# Sheet.net
KiCad netlist of a schematic drawn in Altium Designer
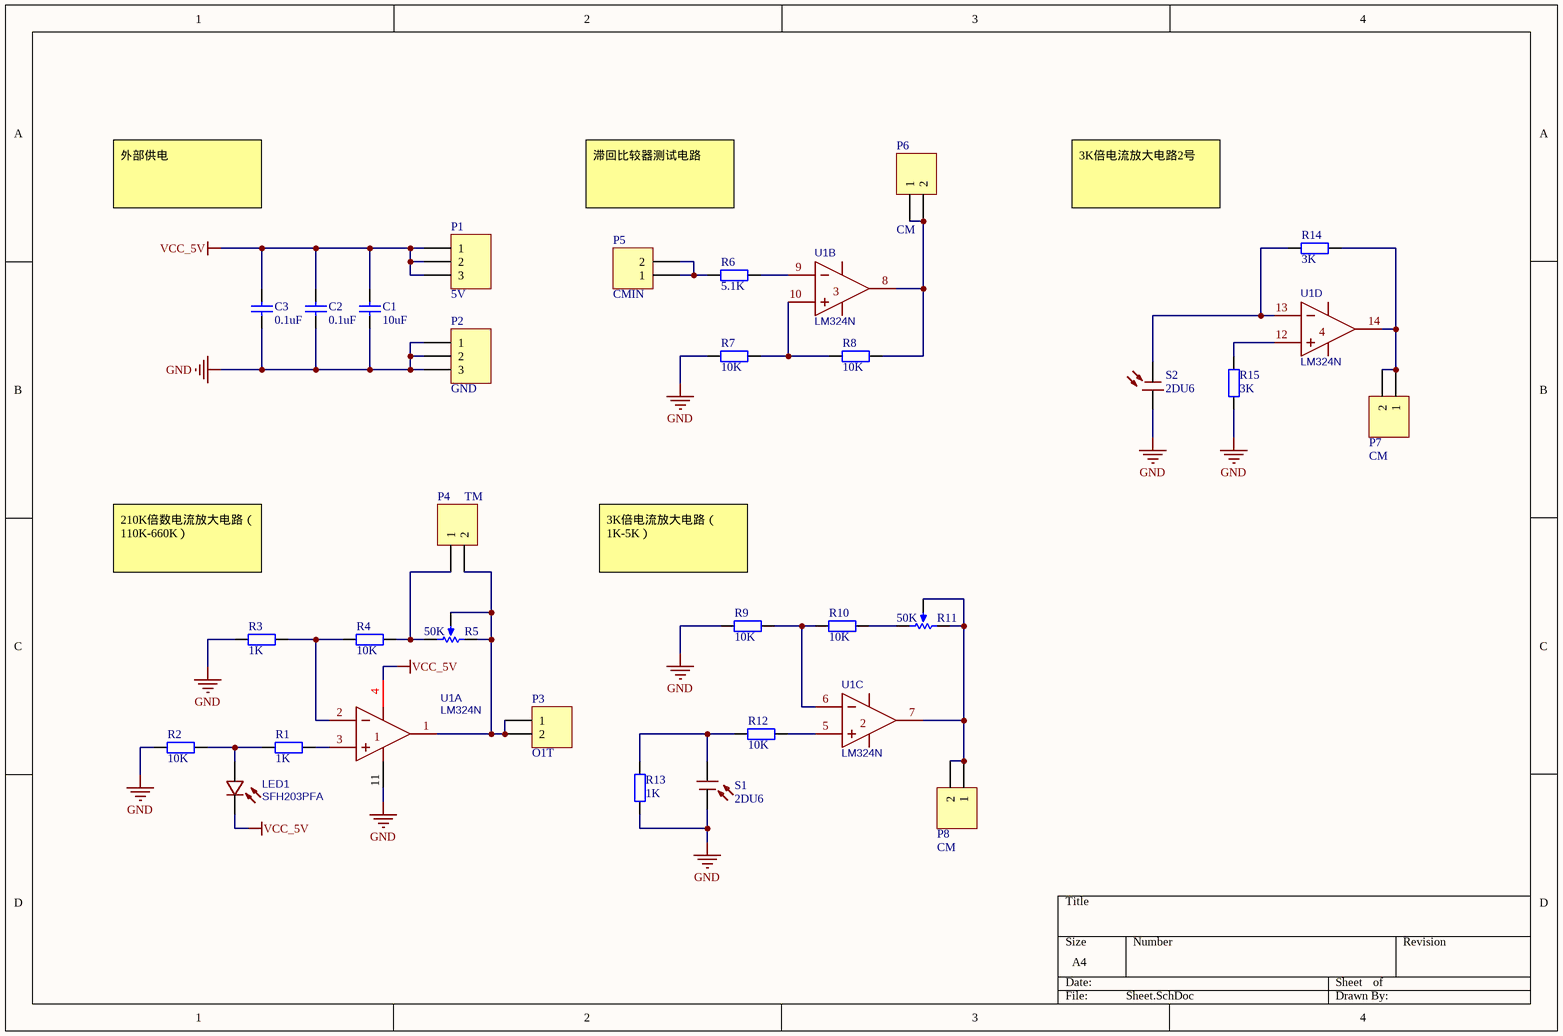
[diagram p0: Sheet.SchDoc]

(export (version "E")
  (design (tool "Eeschema 10.0.6"))
  (components
    (comp (ref "C1")
      (value "10uF")
      (footprint "C1206")
      (description "Capacitor (Semiconductor SIM Model)")
      (fields (field (name "Comment") "Cap Semi") (field (name "PUBLISHER") "Altium Limited"))
      (libsource (lib "Miscellaneous Devices") (part "Cap Semi"))
    )
    (comp (ref "C2")
      (value "0.1uF")
      (footprint "CAP-TH_L5.5-W3.0-P5.00-D0.6")
      (description "Capacitor (Semiconductor SIM Model)")
      (fields (field (name "Comment") "Cap Semi") (field (name "PUBLISHER") "Altium Limited"))
      (libsource (lib "Miscellaneous Devices") (part "Cap Semi"))
    )
    (comp (ref "C3")
      (value "0.1uF")
      (footprint "CAP-TH_L5.5-W3.0-P5.00-D0.6")
      (description "Capacitor (Semiconductor SIM Model)")
      (fields (field (name "Comment") "Cap Semi") (field (name "PUBLISHER") "Altium Limited"))
      (libsource (lib "Miscellaneous Devices") (part "Cap Semi"))
    )
    (comp (ref "LED1")
      (value "SFH203PFA")
      (footprint "LED-TH_BD5.9-P2.54-FD")
      (fields (field (name "BOM_SUPPLIER PART") "C554984") (field (name "CONTRIBUTOR") "LCSC"))
      (libsource (lib "Schlib") (part "SFH203PFA"))
    )
    (comp (ref "P1")
      (value "5V")
      (footprint "HDR1X3")
      (description "Header, 3-Pin")
      (fields (field (name "PUBLISHER") "Altium Limited"))
      (libsource (lib "Miscellaneous Connectors") (part "Header 3"))
    )
    (comp (ref "P2")
      (value "GND")
      (footprint "HDR1X3")
      (description "Header, 3-Pin")
      (fields (field (name "PUBLISHER") "Altium Limited"))
      (libsource (lib "Miscellaneous Connectors") (part "Header 3"))
    )
    (comp (ref "P3")
      (value "O1T")
      (footprint "HDR1X2")
      (description "Header, 2-Pin")
      (fields (field (name "PUBLISHER") "Altium Limited"))
      (libsource (lib "") (part "Header 2_3"))
    )
    (comp (ref "P4")
      (value "TM")
      (footprint "HDR1X2")
      (description "Header, 2-Pin")
      (fields (field (name "PUBLISHER") "Altium Limited"))
      (libsource (lib "") (part "Header 2_2"))
    )
    (comp (ref "P5")
      (value "CMIN")
      (footprint "HDR1X2")
      (description "Header, 2-Pin")
      (fields (field (name "PUBLISHER") "Altium Limited"))
      (libsource (lib "") (part "Header 2_1"))
    )
    (comp (ref "P6")
      (value "CM")
      (footprint "HDR1X2")
      (description "Header, 2-Pin")
      (fields (field (name "PUBLISHER") "Altium Limited"))
      (libsource (lib "") (part "Header 2_2"))
    )
    (comp (ref "P7")
      (value "CM")
      (footprint "HDR1X2")
      (description "Header, 2-Pin")
      (fields (field (name "PUBLISHER") "Altium Limited"))
      (libsource (lib "Miscellaneous Connectors") (part "Header 2"))
    )
    (comp (ref "P8")
      (value "CM")
      (footprint "HDR1X2")
      (description "Header, 2-Pin")
      (fields (field (name "PUBLISHER") "Altium Limited"))
      (libsource (lib "Miscellaneous Connectors") (part "Header 2"))
    )
    (comp (ref "R1")
      (value "1K")
      (footprint "AXIAL-0.4")
      (description "Resistor")
      (fields (field (name "Comment") "Res2") (field (name "PUBLISHER") "Altium Limited"))
      (libsource (lib "") (part "Res2_2"))
    )
    (comp (ref "R2")
      (value "10K")
      (footprint "AXIAL-0.4")
      (description "Resistor")
      (fields (field (name "Comment") "Res2") (field (name "PUBLISHER") "Altium Limited"))
      (libsource (lib "Miscellaneous Devices") (part "Res2"))
    )
    (comp (ref "R3")
      (value "1K")
      (footprint "AXIAL-0.4")
      (description "Resistor")
      (fields (field (name "Comment") "Res2") (field (name "PUBLISHER") "Altium Limited"))
      (libsource (lib "Miscellaneous Devices") (part "Res2"))
    )
    (comp (ref "R4")
      (value "10K")
      (footprint "AXIAL-0.4")
      (description "Resistor")
      (fields (field (name "Comment") "Res2") (field (name "PUBLISHER") "Altium Limited"))
      (libsource (lib "Miscellaneous Devices") (part "Res2"))
    )
    (comp (ref "R5")
      (value "50K")
      (footprint "RES-ADJ-TH_3P-L10.0-W10.0-P2.50-L")
      (description "Potentiometer")
      (fields (field (name "Comment") "RPot") (field (name "PUBLISHER") "Altium Limited"))
      (libsource (lib "Miscellaneous Devices") (part "RPot"))
    )
    (comp (ref "R6")
      (value "5.1K")
      (footprint "AXIAL-0.4")
      (description "Resistor")
      (fields (field (name "Comment") "Res2") (field (name "PUBLISHER") "Altium Limited"))
      (libsource (lib "Miscellaneous Devices") (part "Res2"))
    )
    (comp (ref "R7")
      (value "10K")
      (footprint "AXIAL-0.4")
      (description "Resistor")
      (fields (field (name "Comment") "Res2") (field (name "PUBLISHER") "Altium Limited"))
      (libsource (lib "Miscellaneous Devices") (part "Res2"))
    )
    (comp (ref "R8")
      (value "10K")
      (footprint "AXIAL-0.4")
      (description "Resistor")
      (fields (field (name "Comment") "Res2") (field (name "PUBLISHER") "Altium Limited"))
      (libsource (lib "Miscellaneous Devices") (part "Res2"))
    )
    (comp (ref "R9")
      (value "10K")
      (footprint "AXIAL-0.4")
      (description "Resistor")
      (fields (field (name "Comment") "Res2") (field (name "PUBLISHER") "Altium Limited"))
      (libsource (lib "Miscellaneous Devices") (part "Res2"))
    )
    (comp (ref "R10")
      (value "10K")
      (footprint "AXIAL-0.4")
      (description "Resistor")
      (fields (field (name "Comment") "Res2") (field (name "PUBLISHER") "Altium Limited"))
      (libsource (lib "Miscellaneous Devices") (part "Res2"))
    )
    (comp (ref "R11")
      (value "50K")
      (footprint "RES-ADJ-TH_3P-L10.0-W10.0-P2.50-L")
      (description "Potentiometer")
      (fields (field (name "Comment") "RPot") (field (name "PUBLISHER") "Altium Limited"))
      (libsource (lib "Miscellaneous Devices") (part "RPot"))
    )
    (comp (ref "R12")
      (value "10K")
      (footprint "AXIAL-0.4")
      (description "Resistor")
      (fields (field (name "Comment") "Res2") (field (name "PUBLISHER") "Altium Limited"))
      (libsource (lib "Miscellaneous Devices") (part "Res2"))
    )
    (comp (ref "R13")
      (value "1K")
      (footprint "AXIAL-0.4")
      (description "Resistor")
      (fields (field (name "Comment") "Res2") (field (name "PUBLISHER") "Altium Limited"))
      (libsource (lib "") (part "Res2_1"))
    )
    (comp (ref "R14")
      (value "3K")
      (footprint "AXIAL-0.4")
      (description "Resistor")
      (fields (field (name "Comment") "Res2") (field (name "PUBLISHER") "Altium Limited"))
      (libsource (lib "Miscellaneous Devices") (part "Res2"))
    )
    (comp (ref "R15")
      (value "3K")
      (footprint "AXIAL-0.4")
      (description "Resistor")
      (fields (field (name "Comment") "Res2") (field (name "PUBLISHER") "Altium Limited"))
      (libsource (lib "") (part "Res2_1"))
    )
    (comp (ref "S1") (value "2DU6") (footprint "2DU6PERSONAL") (libsource (lib "Schlib") (part "2DU6")))
    (comp (ref "S2") (value "2DU6") (footprint "2DU6PERSONAL") (libsource (lib "Schlib") (part "2DU6")))
    (comp (ref "U1")
      (value "LM324N")
      (footprint "DIP-14_L19.4-W6.4-P2.54-LS7.6-BL")
      (fields (field (name "BOM_SUPPLIER PART") "C725320") (field (name "SUBPART_NO") "1"))
      (libsource (lib "Schlib") (part "LM324N"))
    )
  )
  (nets
    (net (code "1") (name "GND") (class "Default")
      (node (ref "C1") (pin "1") (pinfunction "1_1") (pintype "passive"))
      (node (ref "C2") (pin "1") (pinfunction "1_1") (pintype "passive"))
      (node (ref "C3") (pin "1") (pinfunction "1_1") (pintype "passive"))
      (node (ref "P2") (pin "1") (pinfunction "1_1") (pintype "passive"))
      (node (ref "P2") (pin "2") (pinfunction "2_2") (pintype "passive"))
      (node (ref "P2") (pin "3") (pinfunction "3_3") (pintype "passive"))
      (node (ref "R13") (pin "1") (pinfunction "1_1") (pintype "passive"))
      (node (ref "R15") (pin "1") (pinfunction "1_1") (pintype "passive"))
      (node (ref "R2") (pin "1") (pinfunction "1_1") (pintype "passive"))
      (node (ref "R3") (pin "1") (pinfunction "1_1") (pintype "passive"))
      (node (ref "R7") (pin "1") (pinfunction "1_1") (pintype "passive"))
      (node (ref "R9") (pin "1") (pinfunction "1_1") (pintype "passive"))
      (node (ref "S1") (pin "2") (pinfunction "E_2") (pintype "passive"))
      (node (ref "S2") (pin "1") (pinfunction "C_1") (pintype "passive"))
      (node (ref "U1") (pin "11") (pinfunction "GND_11") (pintype "passive"))
    )
    (net (code "2") (name "Net-(LED1-C)") (class "Default")
      (node (ref "LED1") (pin "1") (pinfunction "C_1") (pintype "passive"))
      (node (ref "R1") (pin "2") (pinfunction "2_2") (pintype "passive"))
      (node (ref "R2") (pin "2") (pinfunction "2_2") (pintype "passive"))
    )
    (net (code "3") (name "Net-(P5-Pad1)") (class "Default")
      (node (ref "P5") (pin "1") (pinfunction "1_1") (pintype "passive"))
      (node (ref "P5") (pin "2") (pinfunction "2_2") (pintype "passive"))
      (node (ref "R6") (pin "1") (pinfunction "1_1") (pintype "passive"))
    )
    (net (code "4") (name "Net-(R5-BOT)") (class "Default")
      (node (ref "P4") (pin "1") (pinfunction "1_1") (pintype "passive"))
      (node (ref "R4") (pin "2") (pinfunction "2_2") (pintype "passive"))
      (node (ref "R5") (pin "2") (pinfunction "BOT_2") (pintype "passive"))
    )
    (net (code "5") (name "Net-(R5-TAP)") (class "Default")
      (node (ref "P3") (pin "1") (pinfunction "1_1") (pintype "passive"))
      (node (ref "P3") (pin "2") (pinfunction "2_2") (pintype "passive"))
      (node (ref "P4") (pin "2") (pinfunction "2_2") (pintype "passive"))
      (node (ref "R5") (pin "1") (pinfunction "TOP_1") (pintype "passive"))
      (node (ref "R5") (pin "3") (pinfunction "TAP_3") (pintype "passive"))
      (node (ref "U1") (pin "1") (pinfunction "OUT1_1") (pintype "passive"))
    )
    (net (code "6") (name "Net-(R11-BOT)") (class "Default")
      (node (ref "R10") (pin "2") (pinfunction "2_2") (pintype "passive"))
      (node (ref "R11") (pin "2") (pinfunction "BOT_2") (pintype "passive"))
    )
    (net (code "7") (name "Net-(R11-TAP)") (class "Default")
      (node (ref "P8") (pin "1") (pinfunction "1_1") (pintype "passive"))
      (node (ref "P8") (pin "2") (pinfunction "2_2") (pintype "passive"))
      (node (ref "R11") (pin "1") (pinfunction "TOP_1") (pintype "passive"))
      (node (ref "R11") (pin "3") (pinfunction "TAP_3") (pintype "passive"))
      (node (ref "U1") (pin "7") (pinfunction "OUT2_7") (pintype "passive"))
    )
    (net (code "8") (name "Net-(S1-C)") (class "Default")
      (node (ref "R12") (pin "1") (pinfunction "1_1") (pintype "passive"))
      (node (ref "R13") (pin "2") (pinfunction "2_2") (pintype "passive"))
      (node (ref "S1") (pin "1") (pinfunction "C_1") (pintype "passive"))
    )
    (net (code "9") (name "Net-(S2-E)") (class "Default")
      (node (ref "R14") (pin "1") (pinfunction "1_1") (pintype "passive"))
      (node (ref "S2") (pin "2") (pinfunction "E_2") (pintype "passive"))
      (node (ref "U1") (pin "13") (pinfunction "IN4-_13") (pintype "passive"))
    )
    (net (code "10") (name "Net-(U1A-IN1+)") (class "Default")
      (node (ref "R1") (pin "1") (pinfunction "1_1") (pintype "passive"))
      (node (ref "U1") (pin "3") (pinfunction "IN1+_3") (pintype "passive"))
    )
    (net (code "11") (name "Net-(U1A-IN1-)") (class "Default")
      (node (ref "R3") (pin "2") (pinfunction "2_2") (pintype "passive"))
      (node (ref "R4") (pin "1") (pinfunction "1_1") (pintype "passive"))
      (node (ref "U1") (pin "2") (pinfunction "IN1-_2") (pintype "passive"))
    )
    (net (code "12") (name "Net-(U1B-IN3+)") (class "Default")
      (node (ref "R7") (pin "2") (pinfunction "2_2") (pintype "passive"))
      (node (ref "R8") (pin "1") (pinfunction "1_1") (pintype "passive"))
      (node (ref "U1") (pin "10") (pinfunction "IN3+_10") (pintype "passive"))
    )
    (net (code "13") (name "Net-(U1B-IN3-)") (class "Default")
      (node (ref "R6") (pin "2") (pinfunction "2_2") (pintype "passive"))
      (node (ref "U1") (pin "9") (pinfunction "IN3-_9") (pintype "passive"))
    )
    (net (code "14") (name "Net-(U1B-OUT3)") (class "Default")
      (node (ref "P6") (pin "1") (pinfunction "1_1") (pintype "passive"))
      (node (ref "P6") (pin "2") (pinfunction "2_2") (pintype "passive"))
      (node (ref "R8") (pin "2") (pinfunction "2_2") (pintype "passive"))
      (node (ref "U1") (pin "8") (pinfunction "OUT3_8") (pintype "passive"))
    )
    (net (code "15") (name "Net-(U1C-IN2+)") (class "Default")
      (node (ref "R12") (pin "2") (pinfunction "2_2") (pintype "passive"))
      (node (ref "U1") (pin "5") (pinfunction "IN2+_5") (pintype "passive"))
    )
    (net (code "16") (name "Net-(U1C-IN2-)") (class "Default")
      (node (ref "R10") (pin "1") (pinfunction "1_1") (pintype "passive"))
      (node (ref "R9") (pin "2") (pinfunction "2_2") (pintype "passive"))
      (node (ref "U1") (pin "6") (pinfunction "IN2-_6") (pintype "passive"))
    )
    (net (code "17") (name "Net-(U1D-IN4+)") (class "Default")
      (node (ref "R15") (pin "2") (pinfunction "2_2") (pintype "passive"))
      (node (ref "U1") (pin "12") (pinfunction "IN4+_12") (pintype "passive"))
    )
    (net (code "18") (name "Net-(U1D-OUT4)") (class "Default")
      (node (ref "P7") (pin "1") (pinfunction "1_1") (pintype "passive"))
      (node (ref "P7") (pin "2") (pinfunction "2_2") (pintype "passive"))
      (node (ref "R14") (pin "2") (pinfunction "2_2") (pintype "passive"))
      (node (ref "U1") (pin "14") (pinfunction "OUT4_14") (pintype "passive"))
    )
    (net (code "19") (name "VCC_5V") (class "Default")
      (node (ref "C1") (pin "2") (pinfunction "2_2") (pintype "passive"))
      (node (ref "C2") (pin "2") (pinfunction "2_2") (pintype "passive"))
      (node (ref "C3") (pin "2") (pinfunction "2_2") (pintype "passive"))
      (node (ref "LED1") (pin "2") (pinfunction "E_2") (pintype "passive"))
      (node (ref "P1") (pin "1") (pinfunction "1_1") (pintype "passive"))
      (node (ref "P1") (pin "2") (pinfunction "2_2") (pintype "passive"))
      (node (ref "P1") (pin "3") (pinfunction "3_3") (pintype "passive"))
      (node (ref "U1") (pin "4") (pinfunction "VCC_4") (pintype "passive"))
    )
  )
)
